# caretaker-dimmer.net
KiCad netlist of a schematic drawn in EAGLE
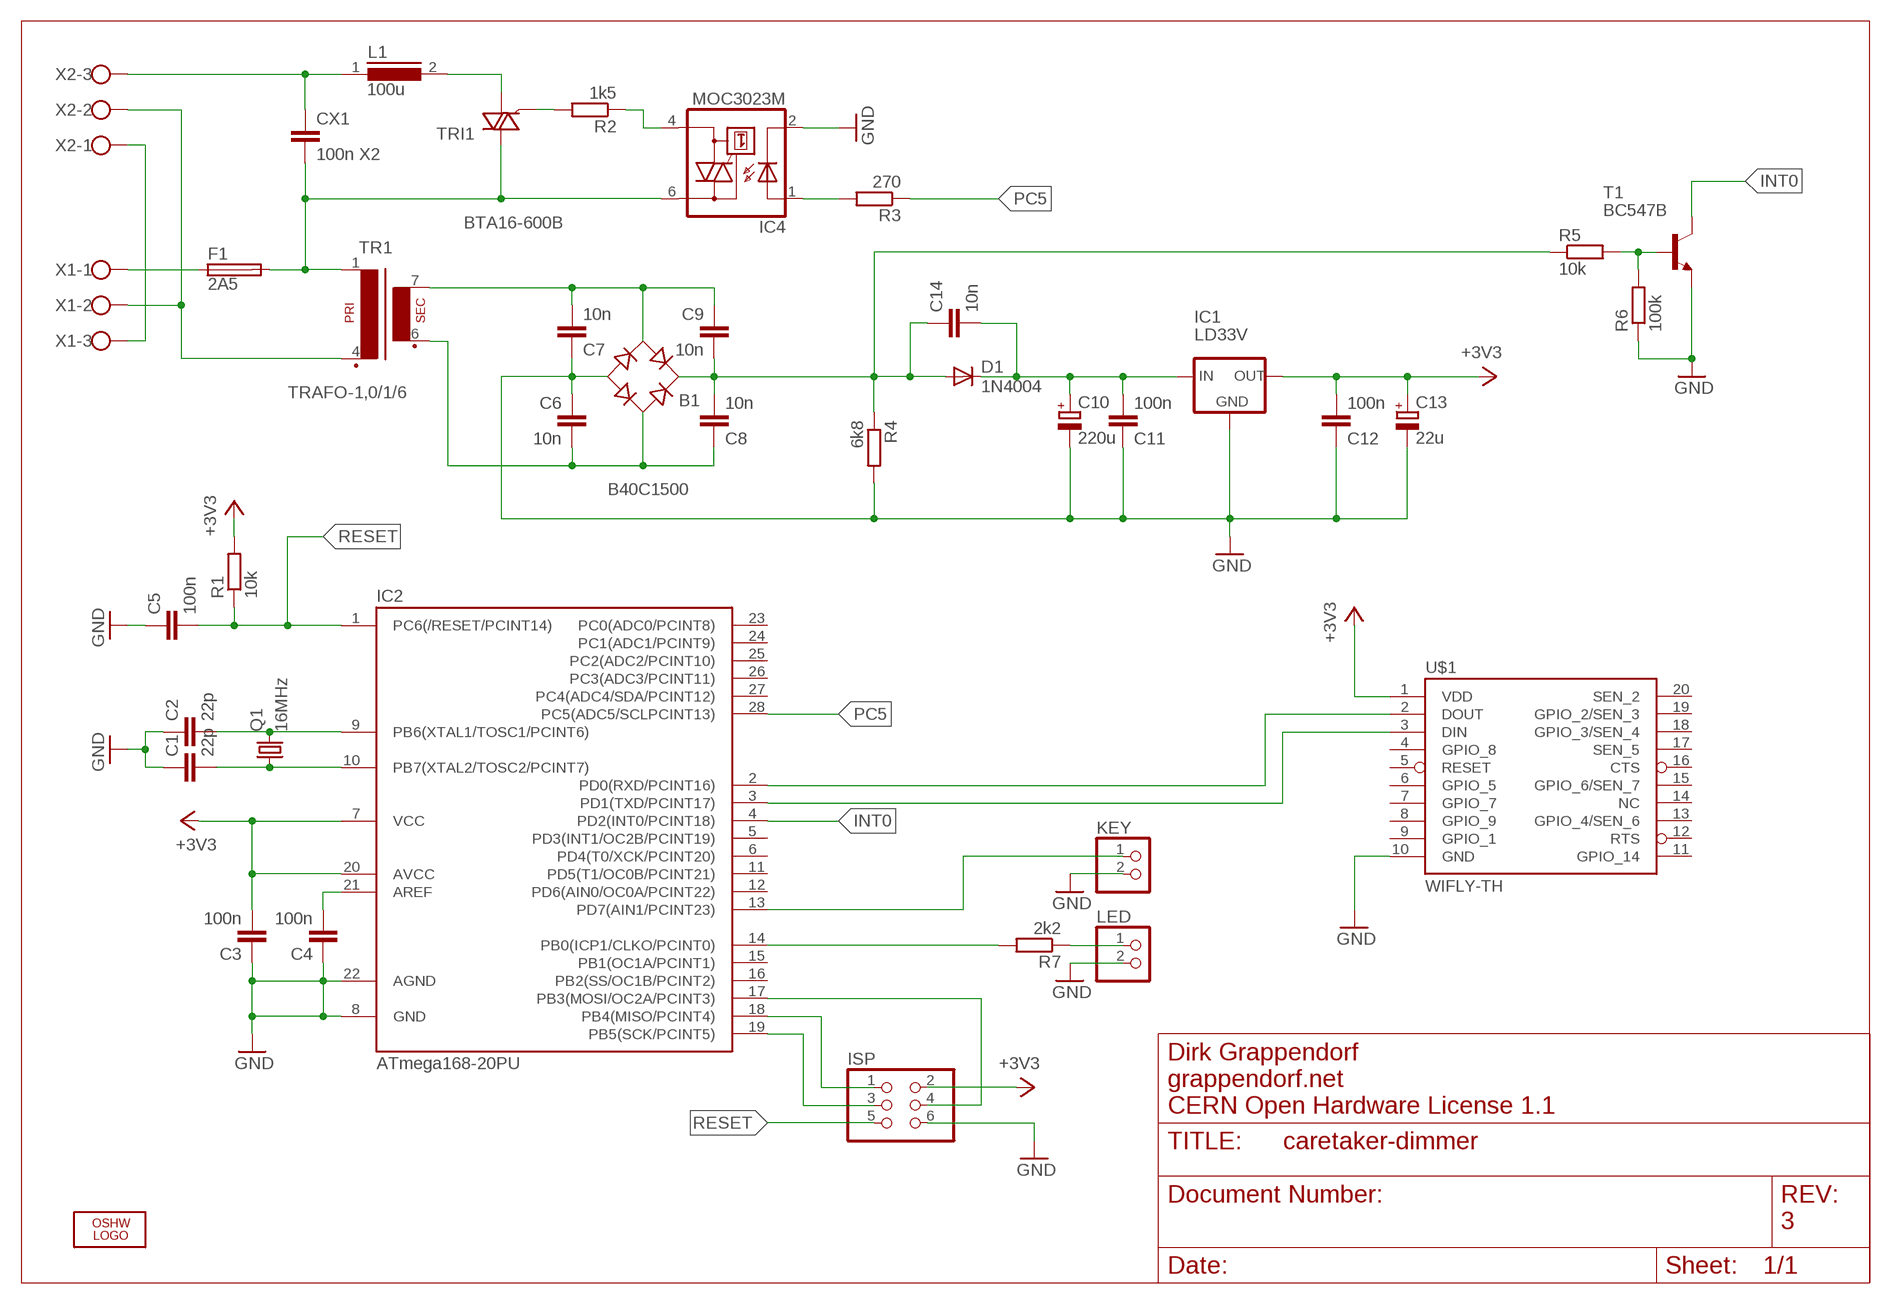
[diagram p0: schematic, sheet 1]

(export (version "E")
  (design (tool "Eeschema 10.0.6"))
  (components
    (comp (ref "B1")
      (value "B40C1500")
      (footprint "eagle-import:2KBB")
      (libsource (lib "eagle-import") (part "RECTIFIER-2KBB"))
    )
    (comp (ref "C1")
      (value "22p")
      (footprint "eagle-import:C025-025X050")
      (libsource (lib "eagle-import") (part "C-EU025-025X050"))
    )
    (comp (ref "C2")
      (value "22p")
      (footprint "eagle-import:C025-025X050")
      (libsource (lib "eagle-import") (part "C-EU025-025X050"))
    )
    (comp (ref "C3")
      (value "100n")
      (footprint "eagle-import:C025-024X044")
      (libsource (lib "eagle-import") (part "C-EU025-024X044"))
    )
    (comp (ref "C4")
      (value "100n")
      (footprint "eagle-import:C025-024X044")
      (libsource (lib "eagle-import") (part "C-EU025-024X044"))
    )
    (comp (ref "C5")
      (value "100n")
      (footprint "eagle-import:C025-024X044")
      (libsource (lib "eagle-import") (part "C-EU025-024X044"))
    )
    (comp (ref "C6")
      (value "10n")
      (footprint "eagle-import:C025-024X044")
      (libsource (lib "eagle-import") (part "C-EU025-024X044"))
    )
    (comp (ref "C7")
      (value "10n")
      (footprint "eagle-import:C025-024X044")
      (libsource (lib "eagle-import") (part "C-EU025-024X044"))
    )
    (comp (ref "C8")
      (value "10n")
      (footprint "eagle-import:C025-024X044")
      (libsource (lib "eagle-import") (part "C-EU025-024X044"))
    )
    (comp (ref "C9")
      (value "10n")
      (footprint "eagle-import:C025-024X044")
      (libsource (lib "eagle-import") (part "C-EU025-024X044"))
    )
    (comp (ref "C10")
      (value "220u")
      (footprint "eagle-import:E3,5-8")
      (libsource (lib "eagle-import") (part "CPOL-EUE3.5-8"))
    )
    (comp (ref "C11")
      (value "100n")
      (footprint "eagle-import:C025-024X044")
      (libsource (lib "eagle-import") (part "C-EU025-024X044"))
    )
    (comp (ref "C12")
      (value "100n")
      (footprint "eagle-import:C025-024X044")
      (libsource (lib "eagle-import") (part "C-EU025-024X044"))
    )
    (comp (ref "C13")
      (value "22u")
      (footprint "eagle-import:E2,5-5")
      (libsource (lib "eagle-import") (part "CPOL-EUE2.5-5"))
    )
    (comp (ref "C14")
      (value "10n")
      (footprint "eagle-import:C025-024X044")
      (libsource (lib "eagle-import") (part "C-EU025-024X044"))
    )
    (comp (ref "CX1")
      (value "100n X2")
      (footprint "eagle-import:XC15B10")
      (libsource (lib "eagle-import") (part "CXXC15B10"))
    )
    (comp (ref "D1")
      (value "1N4004")
      (footprint "eagle-import:D-10")
      (libsource (lib "eagle-import") (part "DIODE-D-10"))
    )
    (comp (ref "F1")
      (value "2A5")
      (footprint "eagle-import:SH22,5")
      (libsource (lib "eagle-import") (part "SH22,5"))
    )
    (comp (ref "IC1")
      (value "LD33V")
      (footprint "eagle-import:78XXL")
      (libsource (lib "eagle-import") (part "V_REG_LD1117VXX"))
    )
    (comp (ref "IC2")
      (value "ATmega168-20PU")
      (footprint "eagle-import:DIL28-3")
      (libsource (lib "eagle-import") (part "ATMEGA48/88/168-PU"))
    )
    (comp (ref "IC4")
      (value "MOC3023M")
      (footprint "eagle-import:DIL06")
      (libsource (lib "eagle-import") (part "MOC30M23"))
    )
    (comp (ref "ISP")
      (value "PINHD-2X3")
      (footprint "eagle-import:2X03")
      (libsource (lib "eagle-import") (part "PINHD-2X3"))
    )
    (comp (ref "KEY")
      (value "PINHD-1X2")
      (footprint "eagle-import:1X02")
      (libsource (lib "eagle-import") (part "PINHD-1X2"))
    )
    (comp (ref "L1")
      (value "100u")
      (footprint "eagle-import:ED22")
      (libsource (lib "eagle-import") (part "ED22"))
    )
    (comp (ref "LED")
      (value "PINHD-1X2")
      (footprint "eagle-import:1X02")
      (libsource (lib "eagle-import") (part "PINHD-1X2"))
    )
    (comp (ref "LOGO1")
      (value "OSHW_LOGO_10MILX0350-NT-BOTTOM")
      (footprint "eagle-import:OSHW_10X350_NOTEXT_BOTTOM")
      (libsource (lib "eagle-import") (part "OSHW_LOGO_10MILX0350-NT-BOTTOM"))
    )
    (comp (ref "Q1")
      (value "16MHz")
      (footprint "eagle-import:HC49U-V")
      (libsource (lib "eagle-import") (part "CRYSTALHC49U-V"))
    )
    (comp (ref "R1")
      (value "10k")
      (footprint "eagle-import:0204_7")
      (libsource (lib "eagle-import") (part "R-EU_0204/7"))
    )
    (comp (ref "R2")
      (value "1k5")
      (footprint "eagle-import:0204_7")
      (libsource (lib "eagle-import") (part "R-EU_0204/7"))
    )
    (comp (ref "R3")
      (value "270")
      (footprint "eagle-import:0204_7")
      (libsource (lib "eagle-import") (part "R-EU_0204/7"))
    )
    (comp (ref "R4")
      (value "6k8")
      (footprint "eagle-import:0204_7")
      (libsource (lib "eagle-import") (part "R-EU_0204/7"))
    )
    (comp (ref "R5")
      (value "10k")
      (footprint "eagle-import:0204_7")
      (libsource (lib "eagle-import") (part "R-EU_0204/7"))
    )
    (comp (ref "R6")
      (value "100k")
      (footprint "eagle-import:0204_7")
      (libsource (lib "eagle-import") (part "R-EU_0204/7"))
    )
    (comp (ref "R7")
      (value "2k2")
      (footprint "eagle-import:0204_7")
      (libsource (lib "eagle-import") (part "R-EU_0204/7"))
    )
    (comp (ref "T1")
      (value "BC547B")
      (footprint "eagle-import:TO92")
      (libsource (lib "eagle-import") (part "BC547B"))
    )
    (comp (ref "TR1")
      (value "TRAFO-1,0/1/6")
      (footprint "eagle-import:TRAFO-1,0_1_6")
      (libsource (lib "eagle-import") (part "TRAFO-1,0/1/6"))
    )
    (comp (ref "TRI1")
      (value "BTA16-600B")
      (footprint "eagle-import:TO220AB")
      (libsource (lib "eagle-import") (part "BT136"))
    )
    (comp (ref "U$1")
      (value "WIFLY-TH")
      (footprint "eagle-import:WIFLY-TH")
      (libsource (lib "eagle-import") (part "WIFLY-TH"))
    )
    (comp (ref "X1")
      (value "W237-103")
      (footprint "eagle-import:W237-103")
      (libsource (lib "eagle-import") (part "W237-103"))
    )
    (comp (ref "X2")
      (value "W237-103")
      (footprint "eagle-import:W237-103")
      (libsource (lib "eagle-import") (part "W237-103"))
    )
  )
  (nets
    (net (code "1") (name "+3V3") (class "Default")
      (node (ref "C12") (pin "2") (pinfunction "2_2") (pintype "passive"))
      (node (ref "C13") (pin "+") (pinfunction "+_+") (pintype "passive"))
      (node (ref "C3") (pin "2") (pinfunction "2_2") (pintype "passive"))
      (node (ref "IC1") (pin "GND") (pinfunction "OUT_GND") (pintype "output"))
      (node (ref "IC2") (pin "20") (pinfunction "AVCC_20") (pintype "passive"))
      (node (ref "IC2") (pin "7") (pinfunction "VCC_7") (pintype "power_in"))
      (node (ref "ISP") (pin "2") (pinfunction "2_2") (pintype "passive"))
      (node (ref "R1") (pin "2") (pinfunction "2_2") (pintype "passive"))
      (node (ref "U$1") (pin "1") (pinfunction "VDD_1") (pintype "power_in"))
    )
    (net (code "2") (name "GND") (class "Default")
      (node (ref "B1") (pin "-") (pinfunction "-_-") (pintype "passive"))
      (node (ref "C1") (pin "1") (pinfunction "1_1") (pintype "passive"))
      (node (ref "C10") (pin "-") (pinfunction "-_-") (pintype "passive"))
      (node (ref "C11") (pin "1") (pinfunction "1_1") (pintype "passive"))
      (node (ref "C12") (pin "1") (pinfunction "1_1") (pintype "passive"))
      (node (ref "C13") (pin "-") (pinfunction "-_-") (pintype "passive"))
      (node (ref "C2") (pin "1") (pinfunction "1_1") (pintype "passive"))
      (node (ref "C3") (pin "1") (pinfunction "1_1") (pintype "passive"))
      (node (ref "C4") (pin "1") (pinfunction "1_1") (pintype "passive"))
      (node (ref "C5") (pin "1") (pinfunction "1_1") (pintype "passive"))
      (node (ref "C6") (pin "1") (pinfunction "1_1") (pintype "passive"))
      (node (ref "C7") (pin "1") (pinfunction "1_1") (pintype "passive"))
      (node (ref "IC1") (pin "IN") (pinfunction "GND_IN") (pintype "input"))
      (node (ref "IC2") (pin "22") (pinfunction "AGND_22") (pintype "power_in"))
      (node (ref "IC2") (pin "8") (pinfunction "GND_8") (pintype "power_in"))
      (node (ref "IC4") (pin "2") (pinfunction "C_2") (pintype "passive"))
      (node (ref "ISP") (pin "6") (pinfunction "6_6") (pintype "passive"))
      (node (ref "KEY") (pin "2") (pinfunction "2_2") (pintype "passive"))
      (node (ref "LED") (pin "2") (pinfunction "2_2") (pintype "passive"))
      (node (ref "R4") (pin "2") (pinfunction "2_2") (pintype "passive"))
      (node (ref "R6") (pin "1") (pinfunction "1_1") (pintype "passive"))
      (node (ref "T1") (pin "1") (pinfunction "E_1") (pintype "passive"))
      (node (ref "U$1") (pin "10") (pinfunction "GND_10") (pintype "power_in"))
    )
    (net (code "3") (name "INT0") (class "Default")
      (node (ref "IC2") (pin "4") (pinfunction "PD2(INT0/PCINT18)_4") (pintype "bidirectional"))
      (node (ref "T1") (pin "3") (pinfunction "C_3") (pintype "passive"))
    )
    (net (code "4") (name "Net-(B1-Pad+)") (class "Default")
      (node (ref "B1") (pin "+") (pinfunction "+_+") (pintype "passive"))
      (node (ref "C14") (pin "1") (pinfunction "1_1") (pintype "passive"))
      (node (ref "C8") (pin "2") (pinfunction "2_2") (pintype "passive"))
      (node (ref "C9") (pin "2") (pinfunction "2_2") (pintype "passive"))
      (node (ref "D1") (pin "A") (pinfunction "A_A") (pintype "passive"))
      (node (ref "R4") (pin "1") (pinfunction "1_1") (pintype "passive"))
      (node (ref "R5") (pin "1") (pinfunction "1_1") (pintype "passive"))
    )
    (net (code "5") (name "Net-(IC1-IN)") (class "Default")
      (node (ref "C10") (pin "+") (pinfunction "+_+") (pintype "passive"))
      (node (ref "C11") (pin "2") (pinfunction "2_2") (pintype "passive"))
      (node (ref "C14") (pin "2") (pinfunction "2_2") (pintype "passive"))
      (node (ref "D1") (pin "C") (pinfunction "C_C") (pintype "passive"))
      (node (ref "IC1") (pin "OUT") (pinfunction "IN_OUT") (pintype "input"))
    )
    (net (code "6") (name "Net-(IC2-AREF)") (class "Default")
      (node (ref "C4") (pin "2") (pinfunction "2_2") (pintype "passive"))
      (node (ref "IC2") (pin "21") (pinfunction "AREF_21") (pintype "passive"))
    )
    (net (code "7") (name "Net-(IC2-PB0(ICP1{slash}CLKO{slash}PCINT0))") (class "Default")
      (node (ref "IC2") (pin "14") (pinfunction "PB0(ICP1/CLKO/PCINT0)_14") (pintype "bidirectional"))
      (node (ref "R7") (pin "2") (pinfunction "2_2") (pintype "passive"))
    )
    (net (code "8") (name "Net-(IC2-PB3(MOSI{slash}OC2A{slash}PCINT3))") (class "Default")
      (node (ref "IC2") (pin "17") (pinfunction "PB3(MOSI/OC2A/PCINT3)_17") (pintype "bidirectional"))
      (node (ref "ISP") (pin "4") (pinfunction "4_4") (pintype "passive"))
    )
    (net (code "9") (name "Net-(IC2-PB4(MISO{slash}PCINT4))") (class "Default")
      (node (ref "IC2") (pin "18") (pinfunction "PB4(MISO/PCINT4)_18") (pintype "bidirectional"))
      (node (ref "ISP") (pin "1") (pinfunction "1_1") (pintype "passive"))
    )
    (net (code "10") (name "Net-(IC2-PB5(SCK{slash}PCINT5))") (class "Default")
      (node (ref "IC2") (pin "19") (pinfunction "PB5(SCK/PCINT5)_19") (pintype "bidirectional"))
      (node (ref "ISP") (pin "3") (pinfunction "3_3") (pintype "passive"))
    )
    (net (code "11") (name "Net-(IC2-PB6(XTAL1{slash}TOSC1{slash}PCINT6))") (class "Default")
      (node (ref "C2") (pin "2") (pinfunction "2_2") (pintype "passive"))
      (node (ref "IC2") (pin "9") (pinfunction "PB6(XTAL1/TOSC1/PCINT6)_9") (pintype "bidirectional"))
      (node (ref "Q1") (pin "2") (pinfunction "2_2") (pintype "passive"))
    )
    (net (code "12") (name "Net-(IC2-PB7(XTAL2{slash}TOSC2{slash}PCINT7))") (class "Default")
      (node (ref "C1") (pin "2") (pinfunction "2_2") (pintype "passive"))
      (node (ref "IC2") (pin "10") (pinfunction "PB7(XTAL2/TOSC2/PCINT7)_10") (pintype "bidirectional"))
      (node (ref "Q1") (pin "1") (pinfunction "1_1") (pintype "passive"))
    )
    (net (code "13") (name "Net-(IC2-PD0(RXD{slash}PCINT16))") (class "Default")
      (node (ref "IC2") (pin "2") (pinfunction "PD0(RXD/PCINT16)_2") (pintype "bidirectional"))
      (node (ref "U$1") (pin "2") (pinfunction "DOUT_2") (pintype "output"))
    )
    (net (code "14") (name "Net-(IC2-PD1(TXD{slash}PCINT17))") (class "Default")
      (node (ref "IC2") (pin "3") (pinfunction "PD1(TXD/PCINT17)_3") (pintype "bidirectional"))
      (node (ref "U$1") (pin "3") (pinfunction "DIN_3") (pintype "input"))
    )
    (net (code "15") (name "Net-(IC2-PD7(AIN1{slash}PCINT23))") (class "Default")
      (node (ref "IC2") (pin "13") (pinfunction "PD7(AIN1/PCINT23)_13") (pintype "bidirectional"))
      (node (ref "KEY") (pin "1") (pinfunction "1_1") (pintype "passive"))
    )
    (net (code "16") (name "Net-(IC4-A)") (class "Default")
      (node (ref "IC4") (pin "1") (pinfunction "A_1") (pintype "passive"))
      (node (ref "R3") (pin "2") (pinfunction "2_2") (pintype "passive"))
    )
    (net (code "17") (name "Net-(IC4-A1)") (class "Default")
      (node (ref "IC4") (pin "4") (pinfunction "A1_4") (pintype "passive"))
      (node (ref "R2") (pin "1") (pinfunction "1_1") (pintype "passive"))
    )
    (net (code "18") (name "Net-(IC4-A2)") (class "Default")
      (node (ref "CX1") (pin "2") (pinfunction "2_2") (pintype "passive"))
      (node (ref "F1") (pin "2") (pinfunction "2_2") (pintype "passive"))
      (node (ref "IC4") (pin "6") (pinfunction "A2_6") (pintype "passive"))
      (node (ref "TR1") (pin "1") (pinfunction "P1_1") (pintype "passive"))
      (node (ref "TRI1") (pin "2") (pinfunction "A2_2") (pintype "passive"))
    )
    (net (code "19") (name "Net-(LED-Pad1)") (class "Default")
      (node (ref "LED") (pin "1") (pinfunction "1_1") (pintype "passive"))
      (node (ref "R7") (pin "1") (pinfunction "1_1") (pintype "passive"))
    )
    (net (code "20") (name "Net-(T1-B)") (class "Default")
      (node (ref "R5") (pin "2") (pinfunction "2_2") (pintype "passive"))
      (node (ref "R6") (pin "2") (pinfunction "2_2") (pintype "passive"))
      (node (ref "T1") (pin "2") (pinfunction "B_2") (pintype "passive"))
    )
    (net (code "21") (name "Net-(TR1-P2)") (class "Default")
      (node (ref "TR1") (pin "4") (pinfunction "P2_4") (pintype "passive"))
      (node (ref "X1") (pin "2") (pinfunction "KL_2") (pintype "passive"))
      (node (ref "X2") (pin "2") (pinfunction "KL_2") (pintype "passive"))
    )
    (net (code "22") (name "Net-(TR1-S3)") (class "Default")
      (node (ref "B1") (pin "AC1") (pinfunction "AC1_AC1") (pintype "passive"))
      (node (ref "C6") (pin "2") (pinfunction "2_2") (pintype "passive"))
      (node (ref "C8") (pin "1") (pinfunction "1_1") (pintype "passive"))
      (node (ref "TR1") (pin "6") (pinfunction "S3_6") (pintype "passive"))
    )
    (net (code "23") (name "Net-(TR1-S4)") (class "Default")
      (node (ref "B1") (pin "AC2") (pinfunction "AC2_AC2") (pintype "passive"))
      (node (ref "C7") (pin "2") (pinfunction "2_2") (pintype "passive"))
      (node (ref "C9") (pin "1") (pinfunction "1_1") (pintype "passive"))
      (node (ref "TR1") (pin "7") (pinfunction "S4_7") (pintype "passive"))
    )
    (net (code "24") (name "Net-(TRI1-A1)") (class "Default")
      (node (ref "L1") (pin "2") (pinfunction "2_2") (pintype "passive"))
      (node (ref "TRI1") (pin "1") (pinfunction "A1_1") (pintype "passive"))
    )
    (net (code "25") (name "Net-(TRI1-G)") (class "Default")
      (node (ref "R2") (pin "2") (pinfunction "2_2") (pintype "passive"))
      (node (ref "TRI1") (pin "3") (pinfunction "G_3") (pintype "passive"))
    )
    (net (code "26") (name "Net-(X1A-KL)") (class "Default")
      (node (ref "F1") (pin "1") (pinfunction "1_1") (pintype "passive"))
      (node (ref "X1") (pin "1") (pinfunction "KL_1") (pintype "passive"))
    )
    (net (code "27") (name "Net-(X1C-KL)") (class "Default")
      (node (ref "X1") (pin "3") (pinfunction "KL_3") (pintype "passive"))
      (node (ref "X2") (pin "1") (pinfunction "KL_1") (pintype "passive"))
    )
    (net (code "28") (name "Net-(X2C-KL)") (class "Default")
      (node (ref "CX1") (pin "1") (pinfunction "1_1") (pintype "passive"))
      (node (ref "L1") (pin "1") (pinfunction "1_1") (pintype "passive"))
      (node (ref "X2") (pin "3") (pinfunction "KL_3") (pintype "passive"))
    )
    (net (code "29") (name "PC5") (class "Default")
      (node (ref "IC2") (pin "28") (pinfunction "PC5(ADC5/SCLPCINT13)_28") (pintype "bidirectional"))
      (node (ref "R3") (pin "1") (pinfunction "1_1") (pintype "passive"))
    )
    (net (code "30") (name "RESET") (class "Default")
      (node (ref "C5") (pin "2") (pinfunction "2_2") (pintype "passive"))
      (node (ref "IC2") (pin "1") (pinfunction "PC6(/RESET/PCINT14)_1") (pintype "bidirectional"))
      (node (ref "ISP") (pin "5") (pinfunction "5_5") (pintype "passive"))
      (node (ref "R1") (pin "1") (pinfunction "1_1") (pintype "passive"))
    )
    (net (code "31") (name "unconnected-(IC2-PB1(OC1A{slash}PCINT1)-Pad15)") (class "Default")
      (node (ref "IC2") (pin "15") (pinfunction "PB1(OC1A/PCINT1)_15") (pintype "bidirectional"))
    )
    (net (code "32") (name "unconnected-(IC2-PB2(SS{slash}OC1B{slash}PCINT2)-Pad16)") (class "Default")
      (node (ref "IC2") (pin "16") (pinfunction "PB2(SS/OC1B/PCINT2)_16") (pintype "bidirectional"))
    )
    (net (code "33") (name "unconnected-(IC2-PC0(ADC0{slash}PCINT8)-Pad23)") (class "Default")
      (node (ref "IC2") (pin "23") (pinfunction "PC0(ADC0/PCINT8)_23") (pintype "bidirectional"))
    )
    (net (code "34") (name "unconnected-(IC2-PC1(ADC1{slash}PCINT9)-Pad24)") (class "Default")
      (node (ref "IC2") (pin "24") (pinfunction "PC1(ADC1/PCINT9)_24") (pintype "bidirectional"))
    )
    (net (code "35") (name "unconnected-(IC2-PC2(ADC2{slash}PCINT10)-Pad25)") (class "Default")
      (node (ref "IC2") (pin "25") (pinfunction "PC2(ADC2/PCINT10)_25") (pintype "bidirectional"))
    )
    (net (code "36") (name "unconnected-(IC2-PC3(ADC3{slash}PCINT11)-Pad26)") (class "Default")
      (node (ref "IC2") (pin "26") (pinfunction "PC3(ADC3/PCINT11)_26") (pintype "bidirectional"))
    )
    (net (code "37") (name "unconnected-(IC2-PC4(ADC4{slash}SDA{slash}PCINT12)-Pad27)") (class "Default")
      (node (ref "IC2") (pin "27") (pinfunction "PC4(ADC4/SDA/PCINT12)_27") (pintype "bidirectional"))
    )
    (net (code "38") (name "unconnected-(IC2-PD3(INT1{slash}OC2B{slash}PCINT19)-Pad5)") (class "Default")
      (node (ref "IC2") (pin "5") (pinfunction "PD3(INT1/OC2B/PCINT19)_5") (pintype "bidirectional"))
    )
    (net (code "39") (name "unconnected-(IC2-PD4(T0{slash}XCK{slash}PCINT20)-Pad6)") (class "Default")
      (node (ref "IC2") (pin "6") (pinfunction "PD4(T0/XCK/PCINT20)_6") (pintype "bidirectional"))
    )
    (net (code "40") (name "unconnected-(IC2-PD5(T1{slash}OC0B{slash}PCINT21)-Pad11)") (class "Default")
      (node (ref "IC2") (pin "11") (pinfunction "PD5(T1/OC0B/PCINT21)_11") (pintype "bidirectional"))
    )
    (net (code "41") (name "unconnected-(IC2-PD6(AIN0{slash}OC0A{slash}PCINT22)-Pad12)") (class "Default")
      (node (ref "IC2") (pin "12") (pinfunction "PD6(AIN0/OC0A/PCINT22)_12") (pintype "bidirectional"))
    )
    (net (code "42") (name "unconnected-(U$1-CTS-Pad16)") (class "Default")
      (node (ref "U$1") (pin "16") (pinfunction "CTS_16") (pintype "input"))
    )
    (net (code "43") (name "unconnected-(U$1-GPIO_1-Pad9)") (class "Default")
      (node (ref "U$1") (pin "9") (pinfunction "GPIO_1_9") (pintype "bidirectional"))
    )
    (net (code "44") (name "unconnected-(U$1-GPIO_2{slash}SEN_3-Pad19)") (class "Default")
      (node (ref "U$1") (pin "19") (pinfunction "GPIO_2/SEN_3_19") (pintype "bidirectional"))
    )
    (net (code "45") (name "unconnected-(U$1-GPIO_3{slash}SEN_4-Pad18)") (class "Default")
      (node (ref "U$1") (pin "18") (pinfunction "GPIO_3/SEN_4_18") (pintype "bidirectional"))
    )
    (net (code "46") (name "unconnected-(U$1-GPIO_4{slash}SEN_6-Pad13)") (class "Default")
      (node (ref "U$1") (pin "13") (pinfunction "GPIO_4/SEN_6_13") (pintype "bidirectional"))
    )
    (net (code "47") (name "unconnected-(U$1-GPIO_5-Pad6)") (class "Default")
      (node (ref "U$1") (pin "6") (pinfunction "GPIO_5_6") (pintype "bidirectional"))
    )
    (net (code "48") (name "unconnected-(U$1-GPIO_6{slash}SEN_7-Pad15)") (class "Default")
      (node (ref "U$1") (pin "15") (pinfunction "GPIO_6/SEN_7_15") (pintype "bidirectional"))
    )
    (net (code "49") (name "unconnected-(U$1-GPIO_7-Pad7)") (class "Default")
      (node (ref "U$1") (pin "7") (pinfunction "GPIO_7_7") (pintype "bidirectional"))
    )
    (net (code "50") (name "unconnected-(U$1-GPIO_8-Pad4)") (class "Default")
      (node (ref "U$1") (pin "4") (pinfunction "GPIO_8_4") (pintype "bidirectional"))
    )
    (net (code "51") (name "unconnected-(U$1-GPIO_9-Pad8)") (class "Default")
      (node (ref "U$1") (pin "8") (pinfunction "GPIO_9_8") (pintype "bidirectional"))
    )
    (net (code "52") (name "unconnected-(U$1-GPIO_14-Pad11)") (class "Default")
      (node (ref "U$1") (pin "11") (pinfunction "GPIO_14_11") (pintype "bidirectional"))
    )
    (net (code "53") (name "unconnected-(U$1-NC-Pad14)") (class "Default")
      (node (ref "U$1") (pin "14") (pinfunction "NC_14") (pintype "bidirectional"))
    )
    (net (code "54") (name "unconnected-(U$1-RESET-Pad5)") (class "Default")
      (node (ref "U$1") (pin "5") (pinfunction "RESET_5") (pintype "input"))
    )
    (net (code "55") (name "unconnected-(U$1-RTS-Pad12)") (class "Default")
      (node (ref "U$1") (pin "12") (pinfunction "RTS_12") (pintype "output"))
    )
    (net (code "56") (name "unconnected-(U$1-SEN_2-Pad20)") (class "Default")
      (node (ref "U$1") (pin "20") (pinfunction "SEN_2_20") (pintype "bidirectional"))
    )
    (net (code "57") (name "unconnected-(U$1-SEN_5-Pad17)") (class "Default")
      (node (ref "U$1") (pin "17") (pinfunction "SEN_5_17") (pintype "bidirectional"))
    )
  )
)
